# PG05__CELLS.net
KiCad netlist of a schematic drawn in Altium Designer
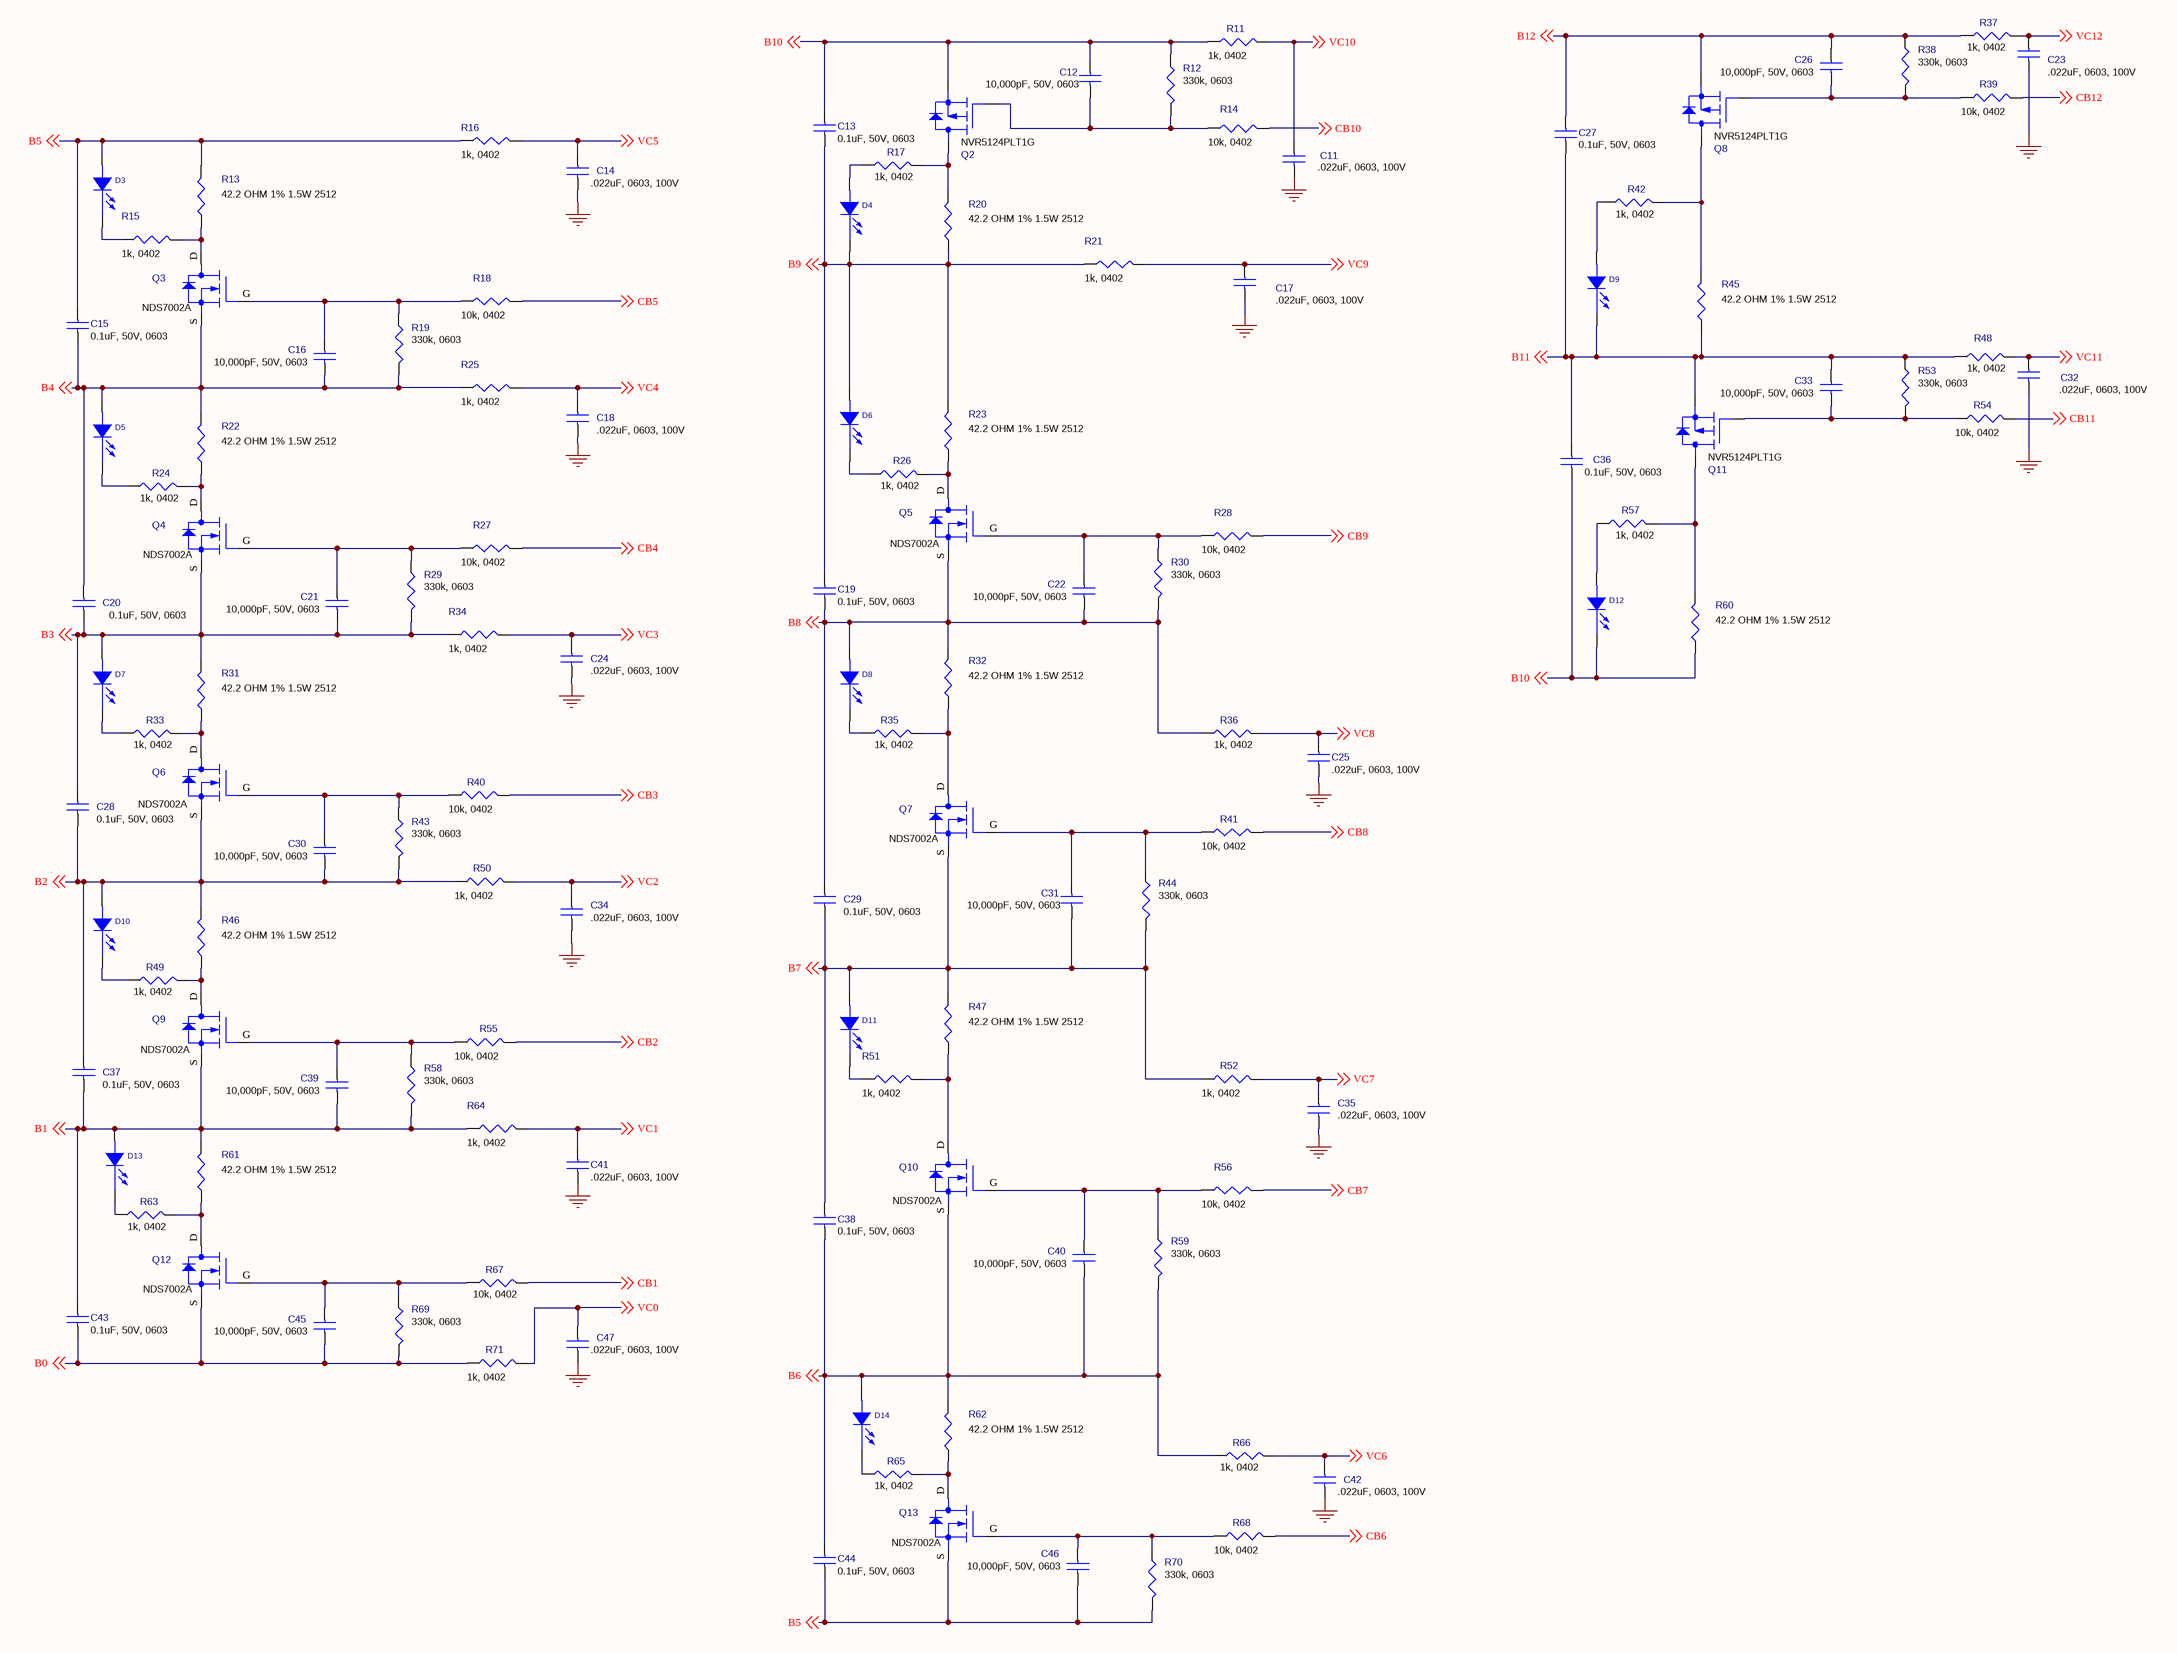
[diagram p0: PG05_ CELLS.SchDoc]

(export (version "E")
  (design (tool "Eeschema 10.0.6"))
  (components
    (comp (ref "C11")
      (value ".022uF, 0603, 100V")
      (footprint "C0603")
      (description "CAP CER 0.022UF 100V X7R 0603")
      (fields
        (field (name "MANUFACTURER") "Murata")
        (field (name "MANUFACTURER PART NUMBER") "GCJ188R72A223KA01D")
      )
      (libsource (lib "*") (part "CAP-Generic-0402"))
    )
    (comp (ref "C12")
      (value "10,000pF, 50V, 0603")
      (footprint "C0603")
      (description "CAP CER 10000PF 50V X7R 0603")
      (fields
        (field (name "MANUFACTURER") "TDK")
        (field (name "MANUFACTURER PART NUMBER") "CGA3E2X7R1H103K080AE")
      )
      (libsource (lib "*") (part "CAP-Generic-0603"))
    )
    (comp (ref "C13")
      (value "0.1uF, 50V, 0603")
      (footprint "C0603")
      (description "CAP CER 0.1UF 50V 10% X7R 0603")
      (fields
        (field (name "MANUFACTURER") "Murata")
        (field (name "MANUFACTURER PART NUMBER") "GCJ188R71E104KA12D")
      )
      (libsource (lib "*") (part "CAP-Generic-0603"))
    )
    (comp (ref "C14")
      (value ".022uF, 0603, 100V")
      (footprint "C0603")
      (description "CAP CER 0.022UF 100V X7R 0603")
      (fields
        (field (name "MANUFACTURER") "Murata")
        (field (name "MANUFACTURER PART NUMBER") "GCJ188R72A223KA01D")
      )
      (libsource (lib "*") (part "CAP-Generic-0402"))
    )
    (comp (ref "C15")
      (value "0.1uF, 50V, 0603")
      (footprint "C0603")
      (description "CAP CER 0.1UF 50V 10% X7R 0603")
      (fields
        (field (name "MANUFACTURER") "Murata")
        (field (name "MANUFACTURER PART NUMBER") "GCJ188R71E104KA12D")
      )
      (libsource (lib "*") (part "CAP-Generic-0603"))
    )
    (comp (ref "C16")
      (value "10,000pF, 50V, 0603")
      (footprint "C0603")
      (description "CAP CER 10000PF 50V X7R 0603")
      (fields
        (field (name "MANUFACTURER") "TDK")
        (field (name "MANUFACTURER PART NUMBER") "CGA3E2X7R1H103K080AE")
      )
      (libsource (lib "*") (part "CAP-Generic-0603"))
    )
    (comp (ref "C17")
      (value ".022uF, 0603, 100V")
      (footprint "C0603")
      (description "CAP CER 0.022UF 100V X7R 0603")
      (fields
        (field (name "MANUFACTURER") "Murata")
        (field (name "MANUFACTURER PART NUMBER") "GCJ188R72A223KA01D")
      )
      (libsource (lib "*") (part "CAP-Generic-0402"))
    )
    (comp (ref "C18")
      (value ".022uF, 0603, 100V")
      (footprint "C0603")
      (description "CAP CER 0.022UF 100V X7R 0603")
      (fields
        (field (name "MANUFACTURER") "Murata")
        (field (name "MANUFACTURER PART NUMBER") "GCJ188R72A223KA01D")
      )
      (libsource (lib "*") (part "CAP-Generic-0402"))
    )
    (comp (ref "C19")
      (value "0.1uF, 50V, 0603")
      (footprint "C0603")
      (description "CAP CER 0.1UF 50V 10% X7R 0603")
      (fields
        (field (name "MANUFACTURER") "Murata")
        (field (name "MANUFACTURER PART NUMBER") "GCJ188R71E104KA12D")
      )
      (libsource (lib "*") (part "CAP-Generic-0603"))
    )
    (comp (ref "C20")
      (value "0.1uF, 50V, 0603")
      (footprint "C0603")
      (description "CAP CER 0.1UF 50V 10% X7R 0603")
      (fields
        (field (name "MANUFACTURER") "Murata")
        (field (name "MANUFACTURER PART NUMBER") "GCJ188R71E104KA12D")
      )
      (libsource (lib "*") (part "CAP-Generic-0603"))
    )
    (comp (ref "C21")
      (value "10,000pF, 50V, 0603")
      (footprint "C0603")
      (description "CAP CER 10000PF 50V X7R 0603")
      (fields
        (field (name "MANUFACTURER") "TDK")
        (field (name "MANUFACTURER PART NUMBER") "CGA3E2X7R1H103K080AE")
      )
      (libsource (lib "*") (part "CAP-Generic-0603"))
    )
    (comp (ref "C22")
      (value "10,000pF, 50V, 0603")
      (footprint "C0603")
      (description "CAP CER 10000PF 50V X7R 0603")
      (fields
        (field (name "MANUFACTURER") "TDK")
        (field (name "MANUFACTURER PART NUMBER") "CGA3E2X7R1H103K080AE")
      )
      (libsource (lib "*") (part "CAP-Generic-0603"))
    )
    (comp (ref "C23")
      (value ".022uF, 0603, 100V")
      (footprint "C0603")
      (description "CAP CER 0.022UF 100V X7R 0603")
      (fields
        (field (name "MANUFACTURER") "Murata")
        (field (name "MANUFACTURER PART NUMBER") "GCJ188R72A223KA01D")
      )
      (libsource (lib "*") (part "CAP-Generic-0402"))
    )
    (comp (ref "C24")
      (value ".022uF, 0603, 100V")
      (footprint "C0603")
      (description "CAP CER 0.022UF 100V X7R 0603")
      (fields
        (field (name "MANUFACTURER") "Murata")
        (field (name "MANUFACTURER PART NUMBER") "GCJ188R72A223KA01D")
      )
      (libsource (lib "*") (part "CAP-Generic-0402"))
    )
    (comp (ref "C25")
      (value ".022uF, 0603, 100V")
      (footprint "C0603")
      (description "CAP CER 0.022UF 100V X7R 0603")
      (fields
        (field (name "MANUFACTURER") "Murata")
        (field (name "MANUFACTURER PART NUMBER") "GCJ188R72A223KA01D")
      )
      (libsource (lib "*") (part "CAP-Generic-0402"))
    )
    (comp (ref "C26")
      (value "10,000pF, 50V, 0603")
      (footprint "C0603")
      (description "CAP CER 10000PF 50V X7R 0603")
      (fields
        (field (name "MANUFACTURER") "TDK")
        (field (name "MANUFACTURER PART NUMBER") "CGA3E2X7R1H103K080AE")
      )
      (libsource (lib "*") (part "CAP-Generic-0603"))
    )
    (comp (ref "C27")
      (value "0.1uF, 50V, 0603")
      (footprint "C0603")
      (description "CAP CER 0.1UF 50V 10% X7R 0603")
      (fields
        (field (name "MANUFACTURER") "Murata")
        (field (name "MANUFACTURER PART NUMBER") "GCJ188R71E104KA12D")
      )
      (libsource (lib "*") (part "CAP-Generic-0603"))
    )
    (comp (ref "C28")
      (value "0.1uF, 50V, 0603")
      (footprint "C0603")
      (description "CAP CER 0.1UF 50V 10% X7R 0603")
      (fields
        (field (name "MANUFACTURER") "Murata")
        (field (name "MANUFACTURER PART NUMBER") "GCJ188R71E104KA12D")
      )
      (libsource (lib "*") (part "CAP-Generic-0603"))
    )
    (comp (ref "C29")
      (value "0.1uF, 50V, 0603")
      (footprint "C0603")
      (description "CAP CER 0.1UF 50V 10% X7R 0603")
      (fields
        (field (name "MANUFACTURER") "Murata")
        (field (name "MANUFACTURER PART NUMBER") "GCJ188R71E104KA12D")
      )
      (libsource (lib "*") (part "CAP-Generic-0603"))
    )
    (comp (ref "C30")
      (value "10,000pF, 50V, 0603")
      (footprint "C0603")
      (description "CAP CER 10000PF 50V X7R 0603")
      (fields
        (field (name "MANUFACTURER") "TDK")
        (field (name "MANUFACTURER PART NUMBER") "CGA3E2X7R1H103K080AE")
      )
      (libsource (lib "*") (part "CAP-Generic-0603"))
    )
    (comp (ref "C31")
      (value "10,000pF, 50V, 0603")
      (footprint "C0603")
      (description "CAP CER 10000PF 50V X7R 0603")
      (fields
        (field (name "MANUFACTURER") "TDK")
        (field (name "MANUFACTURER PART NUMBER") "CGA3E2X7R1H103K080AE")
      )
      (libsource (lib "*") (part "CAP-Generic-0603"))
    )
    (comp (ref "C32")
      (value ".022uF, 0603, 100V")
      (footprint "C0603")
      (description "CAP CER 0.022UF 100V X7R 0603")
      (fields
        (field (name "MANUFACTURER") "Murata")
        (field (name "MANUFACTURER PART NUMBER") "GCJ188R72A223KA01D")
      )
      (libsource (lib "*") (part "CAP-Generic-0402"))
    )
    (comp (ref "C33")
      (value "10,000pF, 50V, 0603")
      (footprint "C0603")
      (description "CAP CER 10000PF 50V X7R 0603")
      (fields
        (field (name "MANUFACTURER") "TDK")
        (field (name "MANUFACTURER PART NUMBER") "CGA3E2X7R1H103K080AE")
      )
      (libsource (lib "*") (part "CAP-Generic-0603"))
    )
    (comp (ref "C34")
      (value ".022uF, 0603, 100V")
      (footprint "C0603")
      (description "CAP CER 0.022UF 100V X7R 0603")
      (fields
        (field (name "MANUFACTURER") "Murata")
        (field (name "MANUFACTURER PART NUMBER") "GCJ188R72A223KA01D")
      )
      (libsource (lib "*") (part "CAP-Generic-0402"))
    )
    (comp (ref "C35")
      (value ".022uF, 0603, 100V")
      (footprint "C0603")
      (description "CAP CER 0.022UF 100V X7R 0603")
      (fields
        (field (name "MANUFACTURER") "Murata")
        (field (name "MANUFACTURER PART NUMBER") "GCJ188R72A223KA01D")
      )
      (libsource (lib "*") (part "CAP-Generic-0402"))
    )
    (comp (ref "C36")
      (value "0.1uF, 50V, 0603")
      (footprint "C0603")
      (description "CAP CER 0.1UF 50V 10% X7R 0603")
      (fields
        (field (name "MANUFACTURER") "Murata")
        (field (name "MANUFACTURER PART NUMBER") "GCJ188R71E104KA12D")
      )
      (libsource (lib "*") (part "CAP-Generic-0603"))
    )
    (comp (ref "C37")
      (value "0.1uF, 50V, 0603")
      (footprint "C0603")
      (description "CAP CER 0.1UF 50V 10% X7R 0603")
      (fields
        (field (name "MANUFACTURER") "Murata")
        (field (name "MANUFACTURER PART NUMBER") "GCJ188R71E104KA12D")
      )
      (libsource (lib "*") (part "CAP-Generic-0603"))
    )
    (comp (ref "C38")
      (value "0.1uF, 50V, 0603")
      (footprint "C0603")
      (description "CAP CER 0.1UF 50V 10% X7R 0603")
      (fields
        (field (name "MANUFACTURER") "Murata")
        (field (name "MANUFACTURER PART NUMBER") "GCJ188R71E104KA12D")
      )
      (libsource (lib "*") (part "CAP-Generic-0603"))
    )
    (comp (ref "C39")
      (value "10,000pF, 50V, 0603")
      (footprint "C0603")
      (description "CAP CER 10000PF 50V X7R 0603")
      (fields
        (field (name "MANUFACTURER") "TDK")
        (field (name "MANUFACTURER PART NUMBER") "CGA3E2X7R1H103K080AE")
      )
      (libsource (lib "*") (part "CAP-Generic-0603"))
    )
    (comp (ref "C40")
      (value "10,000pF, 50V, 0603")
      (footprint "C0603")
      (description "CAP CER 10000PF 50V X7R 0603")
      (fields
        (field (name "MANUFACTURER") "TDK")
        (field (name "MANUFACTURER PART NUMBER") "CGA3E2X7R1H103K080AE")
      )
      (libsource (lib "*") (part "CAP-Generic-0603"))
    )
    (comp (ref "C41")
      (value ".022uF, 0603, 100V")
      (footprint "C0603")
      (description "CAP CER 0.022UF 100V X7R 0603")
      (fields
        (field (name "MANUFACTURER") "Murata")
        (field (name "MANUFACTURER PART NUMBER") "GCJ188R72A223KA01D")
      )
      (libsource (lib "*") (part "CAP-Generic-0402"))
    )
    (comp (ref "C42")
      (value ".022uF, 0603, 100V")
      (footprint "C0603")
      (description "CAP CER 0.022UF 100V X7R 0603")
      (fields
        (field (name "MANUFACTURER") "Murata")
        (field (name "MANUFACTURER PART NUMBER") "GCJ188R72A223KA01D")
      )
      (libsource (lib "*") (part "CAP-Generic-0402"))
    )
    (comp (ref "C43")
      (value "0.1uF, 50V, 0603")
      (footprint "C0603")
      (description "CAP CER 0.1UF 50V 10% X7R 0603")
      (fields
        (field (name "MANUFACTURER") "Murata")
        (field (name "MANUFACTURER PART NUMBER") "GCJ188R71E104KA12D")
      )
      (libsource (lib "*") (part "CAP-Generic-0603"))
    )
    (comp (ref "C44")
      (value "0.1uF, 50V, 0603")
      (footprint "C0603")
      (description "CAP CER 0.1UF 50V 10% X7R 0603")
      (fields
        (field (name "MANUFACTURER") "Murata")
        (field (name "MANUFACTURER PART NUMBER") "GCJ188R71E104KA12D")
      )
      (libsource (lib "*") (part "CAP-Generic-0603"))
    )
    (comp (ref "C45")
      (value "10,000pF, 50V, 0603")
      (footprint "C0603")
      (description "CAP CER 10000PF 50V X7R 0603")
      (fields
        (field (name "MANUFACTURER") "TDK")
        (field (name "MANUFACTURER PART NUMBER") "CGA3E2X7R1H103K080AE")
      )
      (libsource (lib "*") (part "CAP-Generic-0603"))
    )
    (comp (ref "C46")
      (value "10,000pF, 50V, 0603")
      (footprint "C0603")
      (description "CAP CER 10000PF 50V X7R 0603")
      (fields
        (field (name "MANUFACTURER") "TDK")
        (field (name "MANUFACTURER PART NUMBER") "CGA3E2X7R1H103K080AE")
      )
      (libsource (lib "*") (part "CAP-Generic-0603"))
    )
    (comp (ref "C47")
      (value ".022uF, 0603, 100V")
      (footprint "C0603")
      (description "CAP CER 0.022UF 100V X7R 0603")
      (fields
        (field (name "MANUFACTURER") "Murata")
        (field (name "MANUFACTURER PART NUMBER") "GCJ188R72A223KA01D")
      )
      (libsource (lib "*") (part "CAP-Generic-0402"))
    )
    (comp (ref "D3")
      (value "SML-P12MTT86R, 0402")
      (footprint "D0402")
      (libsource (lib "M2_V8_BMU_V1.0") (part "LED-GENERIC"))
    )
    (comp (ref "D4")
      (value "SML-P12MTT86R, 0402")
      (footprint "D0402")
      (libsource (lib "M2_V8_BMU_V1.0") (part "LED-GENERIC"))
    )
    (comp (ref "D5")
      (value "SML-P12MTT86R, 0402")
      (footprint "D0402")
      (libsource (lib "M2_V8_BMU_V1.0") (part "LED-GENERIC"))
    )
    (comp (ref "D6")
      (value "SML-P12MTT86R, 0402")
      (footprint "D0402")
      (libsource (lib "M2_V8_BMU_V1.0") (part "LED-GENERIC"))
    )
    (comp (ref "D7")
      (value "SML-P12MTT86R, 0402")
      (footprint "D0402")
      (libsource (lib "M2_V8_BMU_V1.0") (part "LED-GENERIC"))
    )
    (comp (ref "D8")
      (value "SML-P12MTT86R, 0402")
      (footprint "D0402")
      (libsource (lib "M2_V8_BMU_V1.0") (part "LED-GENERIC"))
    )
    (comp (ref "D9")
      (value "SML-P12MTT86R, 0402")
      (footprint "D0402")
      (libsource (lib "M2_V8_BMU_V1.0") (part "LED-GENERIC"))
    )
    (comp (ref "D10")
      (value "SML-P12MTT86R, 0402")
      (footprint "D0402")
      (libsource (lib "M2_V8_BMU_V1.0") (part "LED-GENERIC"))
    )
    (comp (ref "D11")
      (value "SML-P12MTT86R, 0402")
      (footprint "D0402")
      (libsource (lib "M2_V8_BMU_V1.0") (part "LED-GENERIC"))
    )
    (comp (ref "D12")
      (value "SML-P12MTT86R, 0402")
      (footprint "D0402")
      (libsource (lib "M2_V8_BMU_V1.0") (part "LED-GENERIC"))
    )
    (comp (ref "D13")
      (value "SML-P12MTT86R, 0402")
      (footprint "D0402")
      (libsource (lib "M2_V8_BMU_V1.0") (part "LED-GENERIC"))
    )
    (comp (ref "D14")
      (value "SML-P12MTT86R, 0402")
      (footprint "D0402")
      (libsource (lib "M2_V8_BMU_V1.0") (part "LED-GENERIC"))
    )
    (comp (ref "Q2")
      (value "NVR5124PLT1G")
      (footprint "SOT-23")
      (description "MOSFET P-CH 60V 1.1A SOT-23")
      (fields (field (name "MANUFACTURER") "ON Semiconductor"))
      (libsource (lib "*") (part "FET-P-CH-Generic_OP4_0"))
    )
    (comp (ref "Q3")
      (value "NDS7002A")
      (footprint "SOT-23")
      (description "MOSFET N-CH 60V 280MA SOT-23")
      (fields (field (name "MANUFACTURER") "ON Semiconductor / Fairchild") (field (name "VOLTAGE") "60V"))
      (libsource (lib "*") (part "FET-NCH-GenericOp2"))
    )
    (comp (ref "Q4")
      (value "NDS7002A")
      (footprint "SOT-23")
      (description "MOSFET N-CH 60V 280MA SOT-23")
      (fields (field (name "MANUFACTURER") "ON Semiconductor / Fairchild") (field (name "VOLTAGE") "60V"))
      (libsource (lib "*") (part "FET-NCH-GenericOp2"))
    )
    (comp (ref "Q5")
      (value "NDS7002A")
      (footprint "SOT-23")
      (description "MOSFET N-CH 60V 280MA SOT-23")
      (fields (field (name "MANUFACTURER") "ON Semiconductor / Fairchild") (field (name "VOLTAGE") "60V"))
      (libsource (lib "*") (part "FET-NCH-GenericOp2"))
    )
    (comp (ref "Q6")
      (value "NDS7002A")
      (footprint "SOT-23")
      (description "MOSFET N-CH 60V 280MA SOT-23")
      (fields (field (name "MANUFACTURER") "ON Semiconductor / Fairchild") (field (name "VOLTAGE") "60V"))
      (libsource (lib "*") (part "FET-NCH-GenericOp2"))
    )
    (comp (ref "Q7")
      (value "NDS7002A")
      (footprint "SOT-23")
      (description "MOSFET N-CH 60V 280MA SOT-23")
      (fields (field (name "MANUFACTURER") "ON Semiconductor / Fairchild") (field (name "VOLTAGE") "60V"))
      (libsource (lib "*") (part "FET-NCH-GenericOp2"))
    )
    (comp (ref "Q8")
      (value "NVR5124PLT1G")
      (footprint "SOT-23")
      (description "MOSFET P-CH 60V 1.1A SOT-23")
      (fields (field (name "MANUFACTURER") "ON Semiconductor"))
      (libsource (lib "*") (part "FET-P-CH-Generic_OP4_0"))
    )
    (comp (ref "Q9")
      (value "NDS7002A")
      (footprint "SOT-23")
      (description "MOSFET N-CH 60V 280MA SOT-23")
      (fields (field (name "MANUFACTURER") "ON Semiconductor / Fairchild") (field (name "VOLTAGE") "60V"))
      (libsource (lib "*") (part "FET-NCH-GenericOp2"))
    )
    (comp (ref "Q10")
      (value "NDS7002A")
      (footprint "SOT-23")
      (description "MOSFET N-CH 60V 280MA SOT-23")
      (fields (field (name "MANUFACTURER") "ON Semiconductor / Fairchild") (field (name "VOLTAGE") "60V"))
      (libsource (lib "*") (part "FET-NCH-GenericOp2"))
    )
    (comp (ref "Q11")
      (value "NVR5124PLT1G")
      (footprint "SOT-23")
      (description "MOSFET P-CH 60V 1.1A SOT-23")
      (fields (field (name "MANUFACTURER") "ON Semiconductor"))
      (libsource (lib "*") (part "FET-P-CH-Generic_OP4_0"))
    )
    (comp (ref "Q12")
      (value "NDS7002A")
      (footprint "SOT-23")
      (description "MOSFET N-CH 60V 280MA SOT-23")
      (fields (field (name "MANUFACTURER") "ON Semiconductor / Fairchild") (field (name "VOLTAGE") "60V"))
      (libsource (lib "*") (part "FET-NCH-GenericOp2"))
    )
    (comp (ref "Q13")
      (value "NDS7002A")
      (footprint "SOT-23")
      (description "MOSFET N-CH 60V 280MA SOT-23")
      (fields (field (name "MANUFACTURER") "ON Semiconductor / Fairchild") (field (name "VOLTAGE") "60V"))
      (libsource (lib "*") (part "FET-NCH-GenericOp2"))
    )
    (comp (ref "R11")
      (value "1k, 0402")
      (footprint "R0402")
      (description "RES SMD 1K OHM 5% 1/16W 0402")
      (fields
        (field (name "MANUFACTURER") "Yageo")
        (field (name "MANUFACTURER PART NUMBER") "RC0402JR-071KL")
      )
      (libsource (lib "*") (part "R-Generic-0402"))
    )
    (comp (ref "R12")
      (value "330k, 0603")
      (footprint "R0603")
      (description "RES SMD 330K OHM 5% 1/10W 0603")
      (fields
        (field (name "MANUFACTURER") "Yageo")
        (field (name "MANUFACTURER PART NUMBER") "RC0603JR-07330KL")
      )
      (libsource (lib "*") (part "R-Generic-0603"))
    )
    (comp (ref "R13")
      (value "42.2 OHM 1% 1.5W 2512")
      (footprint "2512")
      (description "RES SMD 42.2 OHM 1% 1.5W 2512")
      (fields
        (field (name "MANUFACTURER") "Vishay Dale")
        (field (name "MANUFACTURER PART NUMBER") "CRCW251242R2FKEGHP")
      )
      (libsource (lib "*") (part "R-Generic"))
    )
    (comp (ref "R14")
      (value "10k, 0402")
      (footprint "R0402")
      (description "RES SMD 10K OHM 1% 1/16W 0402")
      (fields
        (field (name "MANUFACTURER") "Vishay Dale")
        (field (name "MANUFACTURER PART NUMBER") "CRCW040210K0FKTD")
      )
      (libsource (lib "Miscellaneous Devices") (part "R-Generic-0402"))
    )
    (comp (ref "R15")
      (value "1k, 0402")
      (footprint "R0402")
      (description "RES SMD 1K OHM 5% 1/16W 0402")
      (fields
        (field (name "MANUFACTURER") "Yageo")
        (field (name "MANUFACTURER PART NUMBER") "RC0402JR-071KL")
      )
      (libsource (lib "*") (part "R-Generic-0402"))
    )
    (comp (ref "R16")
      (value "1k, 0402")
      (footprint "R0402")
      (description "RES SMD 1K OHM 5% 1/16W 0402")
      (fields
        (field (name "MANUFACTURER") "Yageo")
        (field (name "MANUFACTURER PART NUMBER") "RC0402JR-071KL")
      )
      (libsource (lib "*") (part "R-Generic-0402"))
    )
    (comp (ref "R17")
      (value "1k, 0402")
      (footprint "R0402")
      (description "RES SMD 1K OHM 5% 1/16W 0402")
      (fields
        (field (name "MANUFACTURER") "Yageo")
        (field (name "MANUFACTURER PART NUMBER") "RC0402JR-071KL")
      )
      (libsource (lib "*") (part "R-Generic-0402"))
    )
    (comp (ref "R18")
      (value "10k, 0402")
      (footprint "R0402")
      (description "RES SMD 10K OHM 1% 1/16W 0402")
      (fields
        (field (name "MANUFACTURER") "Vishay Dale")
        (field (name "MANUFACTURER PART NUMBER") "CRCW040210K0FKTD")
      )
      (libsource (lib "Miscellaneous Devices") (part "R-Generic-0402"))
    )
    (comp (ref "R19")
      (value "330k, 0603")
      (footprint "R0603")
      (description "RES SMD 330K OHM 5% 1/10W 0603")
      (fields
        (field (name "MANUFACTURER") "Yageo")
        (field (name "MANUFACTURER PART NUMBER") "RC0603JR-07330KL")
      )
      (libsource (lib "*") (part "R-Generic-0603"))
    )
    (comp (ref "R20")
      (value "42.2 OHM 1% 1.5W 2512")
      (footprint "2512")
      (description "RES SMD 42.2 OHM 1% 1.5W 2512")
      (fields
        (field (name "MANUFACTURER") "Vishay Dale")
        (field (name "MANUFACTURER PART NUMBER") "CRCW251242R2FKEGHP")
      )
      (libsource (lib "*") (part "R-Generic"))
    )
    (comp (ref "R21")
      (value "1k, 0402")
      (footprint "R0402")
      (description "RES SMD 1K OHM 5% 1/16W 0402")
      (fields
        (field (name "MANUFACTURER") "Yageo")
        (field (name "MANUFACTURER PART NUMBER") "RC0402JR-071KL")
      )
      (libsource (lib "*") (part "R-Generic-0402"))
    )
    (comp (ref "R22")
      (value "42.2 OHM 1% 1.5W 2512")
      (footprint "2512")
      (description "RES SMD 42.2 OHM 1% 1.5W 2512")
      (fields
        (field (name "MANUFACTURER") "Vishay Dale")
        (field (name "MANUFACTURER PART NUMBER") "CRCW251242R2FKEGHP")
      )
      (libsource (lib "*") (part "R-Generic"))
    )
    (comp (ref "R23")
      (value "42.2 OHM 1% 1.5W 2512")
      (footprint "2512")
      (description "RES SMD 42.2 OHM 1% 1.5W 2512")
      (fields
        (field (name "MANUFACTURER") "Vishay Dale")
        (field (name "MANUFACTURER PART NUMBER") "CRCW251242R2FKEGHP")
      )
      (libsource (lib "*") (part "R-Generic"))
    )
    (comp (ref "R24")
      (value "1k, 0402")
      (footprint "R0402")
      (description "RES SMD 1K OHM 5% 1/16W 0402")
      (fields
        (field (name "MANUFACTURER") "Yageo")
        (field (name "MANUFACTURER PART NUMBER") "RC0402JR-071KL")
      )
      (libsource (lib "*") (part "R-Generic-0402"))
    )
    (comp (ref "R25")
      (value "1k, 0402")
      (footprint "R0402")
      (description "RES SMD 1K OHM 5% 1/16W 0402")
      (fields
        (field (name "MANUFACTURER") "Yageo")
        (field (name "MANUFACTURER PART NUMBER") "RC0402JR-071KL")
      )
      (libsource (lib "*") (part "R-Generic-0402"))
    )
    (comp (ref "R26")
      (value "1k, 0402")
      (footprint "R0402")
      (description "RES SMD 1K OHM 5% 1/16W 0402")
      (fields
        (field (name "MANUFACTURER") "Yageo")
        (field (name "MANUFACTURER PART NUMBER") "RC0402JR-071KL")
      )
      (libsource (lib "*") (part "R-Generic-0402"))
    )
    (comp (ref "R27")
      (value "10k, 0402")
      (footprint "R0402")
      (description "RES SMD 10K OHM 1% 1/16W 0402")
      (fields
        (field (name "MANUFACTURER") "Vishay Dale")
        (field (name "MANUFACTURER PART NUMBER") "CRCW040210K0FKTD")
      )
      (libsource (lib "Miscellaneous Devices") (part "R-Generic-0402"))
    )
    (comp (ref "R28")
      (value "10k, 0402")
      (footprint "R0402")
      (description "RES SMD 10K OHM 1% 1/16W 0402")
      (fields
        (field (name "MANUFACTURER") "Vishay Dale")
        (field (name "MANUFACTURER PART NUMBER") "CRCW040210K0FKTD")
      )
      (libsource (lib "Miscellaneous Devices") (part "R-Generic-0402"))
    )
    (comp (ref "R29")
      (value "330k, 0603")
      (footprint "R0603")
      (description "RES SMD 330K OHM 5% 1/10W 0603")
      (fields
        (field (name "MANUFACTURER") "Yageo")
        (field (name "MANUFACTURER PART NUMBER") "RC0603JR-07330KL")
      )
      (libsource (lib "*") (part "R-Generic-0603"))
    )
    (comp (ref "R30")
      (value "330k, 0603")
      (footprint "R0603")
      (description "RES SMD 330K OHM 5% 1/10W 0603")
      (fields
        (field (name "MANUFACTURER") "Yageo")
        (field (name "MANUFACTURER PART NUMBER") "RC0603JR-07330KL")
      )
      (libsource (lib "*") (part "R-Generic-0603"))
    )
    (comp (ref "R31")
      (value "42.2 OHM 1% 1.5W 2512")
      (footprint "2512")
      (description "RES SMD 42.2 OHM 1% 1.5W 2512")
      (fields
        (field (name "MANUFACTURER") "Vishay Dale")
        (field (name "MANUFACTURER PART NUMBER") "CRCW251242R2FKEGHP")
      )
      (libsource (lib "*") (part "R-Generic"))
    )
    (comp (ref "R32")
      (value "42.2 OHM 1% 1.5W 2512")
      (footprint "2512")
      (description "RES SMD 42.2 OHM 1% 1.5W 2512")
      (fields
        (field (name "MANUFACTURER") "Vishay Dale")
        (field (name "MANUFACTURER PART NUMBER") "CRCW251242R2FKEGHP")
      )
      (libsource (lib "*") (part "R-Generic"))
    )
    (comp (ref "R33")
      (value "1k, 0402")
      (footprint "R0402")
      (description "RES SMD 1K OHM 5% 1/16W 0402")
      (fields
        (field (name "MANUFACTURER") "Yageo")
        (field (name "MANUFACTURER PART NUMBER") "RC0402JR-071KL")
      )
      (libsource (lib "*") (part "R-Generic-0402"))
    )
    (comp (ref "R34")
      (value "1k, 0402")
      (footprint "R0402")
      (description "RES SMD 1K OHM 5% 1/16W 0402")
      (fields
        (field (name "MANUFACTURER") "Yageo")
        (field (name "MANUFACTURER PART NUMBER") "RC0402JR-071KL")
      )
      (libsource (lib "*") (part "R-Generic-0402"))
    )
    (comp (ref "R35")
      (value "1k, 0402")
      (footprint "R0402")
      (description "RES SMD 1K OHM 5% 1/16W 0402")
      (fields
        (field (name "MANUFACTURER") "Yageo")
        (field (name "MANUFACTURER PART NUMBER") "RC0402JR-071KL")
      )
      (libsource (lib "*") (part "R-Generic-0402"))
    )
    (comp (ref "R36")
      (value "1k, 0402")
      (footprint "R0402")
      (description "RES SMD 1K OHM 5% 1/16W 0402")
      (fields
        (field (name "MANUFACTURER") "Yageo")
        (field (name "MANUFACTURER PART NUMBER") "RC0402JR-071KL")
      )
      (libsource (lib "*") (part "R-Generic-0402"))
    )
    (comp (ref "R37")
      (value "1k, 0402")
      (footprint "R0402")
      (description "RES SMD 1K OHM 5% 1/16W 0402")
      (fields
        (field (name "MANUFACTURER") "Yageo")
        (field (name "MANUFACTURER PART NUMBER") "RC0402JR-071KL")
      )
      (libsource (lib "*") (part "R-Generic-0402"))
    )
    (comp (ref "R38")
      (value "330k, 0603")
      (footprint "R0603")
      (description "RES SMD 330K OHM 5% 1/10W 0603")
      (fields
        (field (name "MANUFACTURER") "Yageo")
        (field (name "MANUFACTURER PART NUMBER") "RC0603JR-07330KL")
      )
      (libsource (lib "*") (part "R-Generic-0603"))
    )
    (comp (ref "R39")
      (value "10k, 0402")
      (footprint "R0402")
      (description "RES SMD 10K OHM 1% 1/16W 0402")
      (fields
        (field (name "MANUFACTURER") "Vishay Dale")
        (field (name "MANUFACTURER PART NUMBER") "CRCW040210K0FKTD")
      )
      (libsource (lib "Miscellaneous Devices") (part "R-Generic-0402"))
    )
    (comp (ref "R40")
      (value "10k, 0402")
      (footprint "R0402")
      (description "RES SMD 10K OHM 1% 1/16W 0402")
      (fields
        (field (name "MANUFACTURER") "Vishay Dale")
        (field (name "MANUFACTURER PART NUMBER") "CRCW040210K0FKTD")
      )
      (libsource (lib "Miscellaneous Devices") (part "R-Generic-0402"))
    )
    (comp (ref "R41")
      (value "10k, 0402")
      (footprint "R0402")
      (description "RES SMD 10K OHM 1% 1/16W 0402")
      (fields
        (field (name "MANUFACTURER") "Vishay Dale")
        (field (name "MANUFACTURER PART NUMBER") "CRCW040210K0FKTD")
      )
      (libsource (lib "Miscellaneous Devices") (part "R-Generic-0402"))
    )
    (comp (ref "R42")
      (value "1k, 0402")
      (footprint "R0402")
      (description "RES SMD 1K OHM 5% 1/16W 0402")
      (fields
        (field (name "MANUFACTURER") "Yageo")
        (field (name "MANUFACTURER PART NUMBER") "RC0402JR-071KL")
      )
      (libsource (lib "*") (part "R-Generic-0402"))
    )
    (comp (ref "R43")
      (value "330k, 0603")
      (footprint "R0603")
      (description "RES SMD 330K OHM 5% 1/10W 0603")
      (fields
        (field (name "MANUFACTURER") "Yageo")
        (field (name "MANUFACTURER PART NUMBER") "RC0603JR-07330KL")
      )
      (libsource (lib "*") (part "R-Generic-0603"))
    )
    (comp (ref "R44")
      (value "330k, 0603")
      (footprint "R0603")
      (description "RES SMD 330K OHM 5% 1/10W 0603")
      (fields
        (field (name "MANUFACTURER") "Yageo")
        (field (name "MANUFACTURER PART NUMBER") "RC0603JR-07330KL")
      )
      (libsource (lib "*") (part "R-Generic-0603"))
    )
    (comp (ref "R45")
      (value "42.2 OHM 1% 1.5W 2512")
      (footprint "2512")
      (description "RES SMD 42.2 OHM 1% 1.5W 2512")
      (fields
        (field (name "MANUFACTURER") "Vishay Dale")
        (field (name "MANUFACTURER PART NUMBER") "CRCW251242R2FKEGHP")
      )
      (libsource (lib "*") (part "R-Generic"))
    )
    (comp (ref "R46")
      (value "42.2 OHM 1% 1.5W 2512")
      (footprint "2512")
      (description "RES SMD 42.2 OHM 1% 1.5W 2512")
      (fields
        (field (name "MANUFACTURER") "Vishay Dale")
        (field (name "MANUFACTURER PART NUMBER") "CRCW251242R2FKEGHP")
      )
      (libsource (lib "*") (part "R-Generic"))
    )
    (comp (ref "R47")
      (value "42.2 OHM 1% 1.5W 2512")
      (footprint "2512")
      (description "RES SMD 42.2 OHM 1% 1.5W 2512")
      (fields
        (field (name "MANUFACTURER") "Vishay Dale")
        (field (name "MANUFACTURER PART NUMBER") "CRCW251242R2FKEGHP")
      )
      (libsource (lib "*") (part "R-Generic"))
    )
    (comp (ref "R48")
      (value "1k, 0402")
      (footprint "R0402")
      (description "RES SMD 1K OHM 5% 1/16W 0402")
      (fields
        (field (name "MANUFACTURER") "Yageo")
        (field (name "MANUFACTURER PART NUMBER") "RC0402JR-071KL")
      )
      (libsource (lib "*") (part "R-Generic-0402"))
    )
    (comp (ref "R49")
      (value "1k, 0402")
      (footprint "R0402")
      (description "RES SMD 1K OHM 5% 1/16W 0402")
      (fields
        (field (name "MANUFACTURER") "Yageo")
        (field (name "MANUFACTURER PART NUMBER") "RC0402JR-071KL")
      )
      (libsource (lib "*") (part "R-Generic-0402"))
    )
    (comp (ref "R50")
      (value "1k, 0402")
      (footprint "R0402")
      (description "RES SMD 1K OHM 5% 1/16W 0402")
      (fields
        (field (name "MANUFACTURER") "Yageo")
        (field (name "MANUFACTURER PART NUMBER") "RC0402JR-071KL")
      )
      (libsource (lib "*") (part "R-Generic-0402"))
    )
    (comp (ref "R51")
      (value "1k, 0402")
      (footprint "R0402")
      (description "RES SMD 1K OHM 5% 1/16W 0402")
      (fields
        (field (name "MANUFACTURER") "Yageo")
        (field (name "MANUFACTURER PART NUMBER") "RC0402JR-071KL")
      )
      (libsource (lib "*") (part "R-Generic-0402"))
    )
    (comp (ref "R52")
      (value "1k, 0402")
      (footprint "R0402")
      (description "RES SMD 1K OHM 5% 1/16W 0402")
      (fields
        (field (name "MANUFACTURER") "Yageo")
        (field (name "MANUFACTURER PART NUMBER") "RC0402JR-071KL")
      )
      (libsource (lib "*") (part "R-Generic-0402"))
    )
    (comp (ref "R53")
      (value "330k, 0603")
      (footprint "R0603")
      (description "RES SMD 330K OHM 5% 1/10W 0603")
      (fields
        (field (name "MANUFACTURER") "Yageo")
        (field (name "MANUFACTURER PART NUMBER") "RC0603JR-07330KL")
      )
      (libsource (lib "*") (part "R-Generic-0603"))
    )
    (comp (ref "R54")
      (value "10k, 0402")
      (footprint "R0402")
      (description "RES SMD 10K OHM 1% 1/16W 0402")
      (fields
        (field (name "MANUFACTURER") "Vishay Dale")
        (field (name "MANUFACTURER PART NUMBER") "CRCW040210K0FKTD")
      )
      (libsource (lib "Miscellaneous Devices") (part "R-Generic-0402"))
    )
    (comp (ref "R55")
      (value "10k, 0402")
      (footprint "R0402")
      (description "RES SMD 10K OHM 1% 1/16W 0402")
      (fields
        (field (name "MANUFACTURER") "Vishay Dale")
        (field (name "MANUFACTURER PART NUMBER") "CRCW040210K0FKTD")
      )
      (libsource (lib "Miscellaneous Devices") (part "R-Generic-0402"))
    )
    (comp (ref "R56")
      (value "10k, 0402")
      (footprint "R0402")
      (description "RES SMD 10K OHM 1% 1/16W 0402")
      (fields
        (field (name "MANUFACTURER") "Vishay Dale")
        (field (name "MANUFACTURER PART NUMBER") "CRCW040210K0FKTD")
      )
      (libsource (lib "Miscellaneous Devices") (part "R-Generic-0402"))
    )
    (comp (ref "R57")
      (value "1k, 0402")
      (footprint "R0402")
      (description "RES SMD 1K OHM 5% 1/16W 0402")
      (fields
        (field (name "MANUFACTURER") "Yageo")
        (field (name "MANUFACTURER PART NUMBER") "RC0402JR-071KL")
      )
      (libsource (lib "*") (part "R-Generic-0402"))
    )
    (comp (ref "R58")
      (value "330k, 0603")
      (footprint "R0603")
      (description "RES SMD 330K OHM 5% 1/10W 0603")
      (fields
        (field (name "MANUFACTURER") "Yageo")
        (field (name "MANUFACTURER PART NUMBER") "RC0603JR-07330KL")
      )
      (libsource (lib "*") (part "R-Generic-0603"))
    )
    (comp (ref "R59")
      (value "330k, 0603")
      (footprint "R0603")
      (description "RES SMD 330K OHM 5% 1/10W 0603")
      (fields
        (field (name "MANUFACTURER") "Yageo")
        (field (name "MANUFACTURER PART NUMBER") "RC0603JR-07330KL")
      )
      (libsource (lib "*") (part "R-Generic-0603"))
    )
    (comp (ref "R60")
      (value "42.2 OHM 1% 1.5W 2512")
      (footprint "2512")
      (description "RES SMD 42.2 OHM 1% 1.5W 2512")
      (fields
        (field (name "MANUFACTURER") "Vishay Dale")
        (field (name "MANUFACTURER PART NUMBER") "CRCW251242R2FKEGHP")
      )
      (libsource (lib "*") (part "R-Generic"))
    )
    (comp (ref "R61")
      (value "42.2 OHM 1% 1.5W 2512")
      (footprint "2512")
      (description "RES SMD 42.2 OHM 1% 1.5W 2512")
      (fields
        (field (name "MANUFACTURER") "Vishay Dale")
        (field (name "MANUFACTURER PART NUMBER") "CRCW251242R2FKEGHP")
      )
      (libsource (lib "*") (part "R-Generic"))
    )
    (comp (ref "R62")
      (value "42.2 OHM 1% 1.5W 2512")
      (footprint "2512")
      (description "RES SMD 42.2 OHM 1% 1.5W 2512")
      (fields
        (field (name "MANUFACTURER") "Vishay Dale")
        (field (name "MANUFACTURER PART NUMBER") "CRCW251242R2FKEGHP")
      )
      (libsource (lib "*") (part "R-Generic"))
    )
    (comp (ref "R63")
      (value "1k, 0402")
      (footprint "R0402")
      (description "RES SMD 1K OHM 5% 1/16W 0402")
      (fields
        (field (name "MANUFACTURER") "Yageo")
        (field (name "MANUFACTURER PART NUMBER") "RC0402JR-071KL")
      )
      (libsource (lib "*") (part "R-Generic-0402"))
    )
    (comp (ref "R64")
      (value "1k, 0402")
      (footprint "R0402")
      (description "RES SMD 1K OHM 5% 1/16W 0402")
      (fields
        (field (name "MANUFACTURER") "Yageo")
        (field (name "MANUFACTURER PART NUMBER") "RC0402JR-071KL")
      )
      (libsource (lib "*") (part "R-Generic-0402"))
    )
    (comp (ref "R65")
      (value "1k, 0402")
      (footprint "R0402")
      (description "RES SMD 1K OHM 5% 1/16W 0402")
      (fields
        (field (name "MANUFACTURER") "Yageo")
        (field (name "MANUFACTURER PART NUMBER") "RC0402JR-071KL")
      )
      (libsource (lib "*") (part "R-Generic-0402"))
    )
    (comp (ref "R66")
      (value "1k, 0402")
      (footprint "R0402")
      (description "RES SMD 1K OHM 5% 1/16W 0402")
      (fields
        (field (name "MANUFACTURER") "Yageo")
        (field (name "MANUFACTURER PART NUMBER") "RC0402JR-071KL")
      )
      (libsource (lib "*") (part "R-Generic-0402"))
    )
    (comp (ref "R67")
      (value "10k, 0402")
      (footprint "R0402")
      (description "RES SMD 10K OHM 1% 1/16W 0402")
      (fields
        (field (name "MANUFACTURER") "Vishay Dale")
        (field (name "MANUFACTURER PART NUMBER") "CRCW040210K0FKTD")
      )
      (libsource (lib "Miscellaneous Devices") (part "R-Generic-0402"))
    )
    (comp (ref "R68")
      (value "10k, 0402")
      (footprint "R0402")
      (description "RES SMD 10K OHM 1% 1/16W 0402")
      (fields
        (field (name "MANUFACTURER") "Vishay Dale")
        (field (name "MANUFACTURER PART NUMBER") "CRCW040210K0FKTD")
      )
      (libsource (lib "Miscellaneous Devices") (part "R-Generic-0402"))
    )
    (comp (ref "R69")
      (value "330k, 0603")
      (footprint "R0603")
      (description "RES SMD 330K OHM 5% 1/10W 0603")
      (fields
        (field (name "MANUFACTURER") "Yageo")
        (field (name "MANUFACTURER PART NUMBER") "RC0603JR-07330KL")
      )
      (libsource (lib "*") (part "R-Generic-0603"))
    )
    (comp (ref "R70")
      (value "330k, 0603")
      (footprint "R0603")
      (description "RES SMD 330K OHM 5% 1/10W 0603")
      (fields
        (field (name "MANUFACTURER") "Yageo")
        (field (name "MANUFACTURER PART NUMBER") "RC0603JR-07330KL")
      )
      (libsource (lib "*") (part "R-Generic-0603"))
    )
    (comp (ref "R71")
      (value "1k, 0402")
      (footprint "R0402")
      (description "RES SMD 1K OHM 5% 1/16W 0402")
      (fields
        (field (name "MANUFACTURER") "Yageo")
        (field (name "MANUFACTURER PART NUMBER") "RC0402JR-071KL")
      )
      (libsource (lib "*") (part "R-Generic-0402"))
    )
  )
  (nets
    (net (code "1") (name "B0") (class "Default")
      (node (ref "C43") (pin "2") (pinfunction "2_2") (pintype "passive"))
      (node (ref "C45") (pin "2") (pinfunction "2_2") (pintype "passive"))
      (node (ref "Q12") (pin "S") (pinfunction "SOURCE_S") (pintype "passive"))
      (node (ref "R69") (pin "2") (pinfunction "2_2") (pintype "passive"))
      (node (ref "R71") (pin "1") (pinfunction "1_1") (pintype "passive"))
    )
    (net (code "2") (name "B1") (class "Default")
      (node (ref "C37") (pin "2") (pinfunction "2_2") (pintype "passive"))
      (node (ref "C39") (pin "2") (pinfunction "2_2") (pintype "passive"))
      (node (ref "C43") (pin "1") (pinfunction "1_1") (pintype "passive"))
      (node (ref "D13") (pin "A") (pinfunction "ANODE_A") (pintype "passive"))
      (node (ref "Q9") (pin "S") (pinfunction "SOURCE_S") (pintype "passive"))
      (node (ref "R58") (pin "2") (pinfunction "2_2") (pintype "passive"))
      (node (ref "R61") (pin "2") (pinfunction "2_2") (pintype "passive"))
      (node (ref "R64") (pin "1") (pinfunction "1_1") (pintype "passive"))
    )
    (net (code "3") (name "B2") (class "Default")
      (node (ref "C28") (pin "2") (pinfunction "2_2") (pintype "passive"))
      (node (ref "C30") (pin "2") (pinfunction "2_2") (pintype "passive"))
      (node (ref "C37") (pin "1") (pinfunction "1_1") (pintype "passive"))
      (node (ref "D10") (pin "A") (pinfunction "ANODE_A") (pintype "passive"))
      (node (ref "Q6") (pin "S") (pinfunction "SOURCE_S") (pintype "passive"))
      (node (ref "R43") (pin "2") (pinfunction "2_2") (pintype "passive"))
      (node (ref "R46") (pin "2") (pinfunction "2_2") (pintype "passive"))
      (node (ref "R50") (pin "1") (pinfunction "1_1") (pintype "passive"))
    )
    (net (code "4") (name "B3") (class "Default")
      (node (ref "C20") (pin "2") (pinfunction "2_2") (pintype "passive"))
      (node (ref "C21") (pin "2") (pinfunction "2_2") (pintype "passive"))
      (node (ref "C28") (pin "1") (pinfunction "1_1") (pintype "passive"))
      (node (ref "D7") (pin "A") (pinfunction "ANODE_A") (pintype "passive"))
      (node (ref "Q4") (pin "S") (pinfunction "SOURCE_S") (pintype "passive"))
      (node (ref "R29") (pin "2") (pinfunction "2_2") (pintype "passive"))
      (node (ref "R31") (pin "2") (pinfunction "2_2") (pintype "passive"))
      (node (ref "R34") (pin "1") (pinfunction "1_1") (pintype "passive"))
    )
    (net (code "5") (name "B4") (class "Default")
      (node (ref "C15") (pin "2") (pinfunction "2_2") (pintype "passive"))
      (node (ref "C16") (pin "2") (pinfunction "2_2") (pintype "passive"))
      (node (ref "C20") (pin "1") (pinfunction "1_1") (pintype "passive"))
      (node (ref "D5") (pin "A") (pinfunction "ANODE_A") (pintype "passive"))
      (node (ref "Q3") (pin "S") (pinfunction "SOURCE_S") (pintype "passive"))
      (node (ref "R19") (pin "2") (pinfunction "2_2") (pintype "passive"))
      (node (ref "R22") (pin "2") (pinfunction "2_2") (pintype "passive"))
      (node (ref "R25") (pin "1") (pinfunction "1_1") (pintype "passive"))
    )
    (net (code "6") (name "B5") (class "Default")
      (node (ref "C15") (pin "1") (pinfunction "1_1") (pintype "passive"))
      (node (ref "C44") (pin "2") (pinfunction "2_2") (pintype "passive"))
      (node (ref "C46") (pin "2") (pinfunction "2_2") (pintype "passive"))
      (node (ref "D3") (pin "A") (pinfunction "ANODE_A") (pintype "passive"))
      (node (ref "Q13") (pin "S") (pinfunction "SOURCE_S") (pintype "passive"))
      (node (ref "R13") (pin "2") (pinfunction "2_2") (pintype "passive"))
      (node (ref "R16") (pin "1") (pinfunction "1_1") (pintype "passive"))
      (node (ref "R70") (pin "2") (pinfunction "2_2") (pintype "passive"))
    )
    (net (code "7") (name "B6") (class "Default")
      (node (ref "C38") (pin "2") (pinfunction "2_2") (pintype "passive"))
      (node (ref "C40") (pin "2") (pinfunction "2_2") (pintype "passive"))
      (node (ref "C44") (pin "1") (pinfunction "1_1") (pintype "passive"))
      (node (ref "D14") (pin "A") (pinfunction "ANODE_A") (pintype "passive"))
      (node (ref "Q10") (pin "S") (pinfunction "SOURCE_S") (pintype "passive"))
      (node (ref "R59") (pin "2") (pinfunction "2_2") (pintype "passive"))
      (node (ref "R62") (pin "2") (pinfunction "2_2") (pintype "passive"))
      (node (ref "R66") (pin "1") (pinfunction "1_1") (pintype "passive"))
    )
    (net (code "8") (name "B7") (class "Default")
      (node (ref "C29") (pin "2") (pinfunction "2_2") (pintype "passive"))
      (node (ref "C31") (pin "2") (pinfunction "2_2") (pintype "passive"))
      (node (ref "C38") (pin "1") (pinfunction "1_1") (pintype "passive"))
      (node (ref "D11") (pin "A") (pinfunction "ANODE_A") (pintype "passive"))
      (node (ref "Q7") (pin "S") (pinfunction "SOURCE_S") (pintype "passive"))
      (node (ref "R44") (pin "2") (pinfunction "2_2") (pintype "passive"))
      (node (ref "R47") (pin "2") (pinfunction "2_2") (pintype "passive"))
      (node (ref "R52") (pin "1") (pinfunction "1_1") (pintype "passive"))
    )
    (net (code "9") (name "B8") (class "Default")
      (node (ref "C19") (pin "2") (pinfunction "2_2") (pintype "passive"))
      (node (ref "C22") (pin "2") (pinfunction "2_2") (pintype "passive"))
      (node (ref "C29") (pin "1") (pinfunction "1_1") (pintype "passive"))
      (node (ref "D8") (pin "A") (pinfunction "ANODE_A") (pintype "passive"))
      (node (ref "Q5") (pin "S") (pinfunction "SOURCE_S") (pintype "passive"))
      (node (ref "R30") (pin "2") (pinfunction "2_2") (pintype "passive"))
      (node (ref "R32") (pin "2") (pinfunction "2_2") (pintype "passive"))
      (node (ref "R36") (pin "1") (pinfunction "1_1") (pintype "passive"))
    )
    (net (code "10") (name "B9") (class "Default")
      (node (ref "C13") (pin "2") (pinfunction "2_2") (pintype "passive"))
      (node (ref "C19") (pin "1") (pinfunction "1_1") (pintype "passive"))
      (node (ref "D4") (pin "C") (pinfunction "CATHODE_C") (pintype "passive"))
      (node (ref "D6") (pin "A") (pinfunction "ANODE_A") (pintype "passive"))
      (node (ref "R20") (pin "1") (pinfunction "1_1") (pintype "passive"))
      (node (ref "R21") (pin "1") (pinfunction "1_1") (pintype "passive"))
      (node (ref "R23") (pin "2") (pinfunction "2_2") (pintype "passive"))
    )
    (net (code "11") (name "B10") (class "Default")
      (node (ref "C12") (pin "1") (pinfunction "1_1") (pintype "passive"))
      (node (ref "C13") (pin "1") (pinfunction "1_1") (pintype "passive"))
      (node (ref "C36") (pin "2") (pinfunction "2_2") (pintype "passive"))
      (node (ref "D12") (pin "C") (pinfunction "CATHODE_C") (pintype "passive"))
      (node (ref "Q2") (pin "S") (pinfunction "S_S") (pintype "passive"))
      (node (ref "R11") (pin "1") (pinfunction "1_1") (pintype "passive"))
      (node (ref "R12") (pin "1") (pinfunction "1_1") (pintype "passive"))
      (node (ref "R60") (pin "1") (pinfunction "1_1") (pintype "passive"))
    )
    (net (code "12") (name "B11") (class "Default")
      (node (ref "C27") (pin "2") (pinfunction "2_2") (pintype "passive"))
      (node (ref "C33") (pin "1") (pinfunction "1_1") (pintype "passive"))
      (node (ref "C36") (pin "1") (pinfunction "1_1") (pintype "passive"))
      (node (ref "D9") (pin "C") (pinfunction "CATHODE_C") (pintype "passive"))
      (node (ref "Q11") (pin "S") (pinfunction "S_S") (pintype "passive"))
      (node (ref "R45") (pin "1") (pinfunction "1_1") (pintype "passive"))
      (node (ref "R48") (pin "1") (pinfunction "1_1") (pintype "passive"))
      (node (ref "R53") (pin "1") (pinfunction "1_1") (pintype "passive"))
    )
    (net (code "13") (name "B12") (class "Default")
      (node (ref "C26") (pin "1") (pinfunction "1_1") (pintype "passive"))
      (node (ref "C27") (pin "1") (pinfunction "1_1") (pintype "passive"))
      (node (ref "Q8") (pin "S") (pinfunction "S_S") (pintype "passive"))
      (node (ref "R37") (pin "1") (pinfunction "1_1") (pintype "passive"))
      (node (ref "R38") (pin "1") (pinfunction "1_1") (pintype "passive"))
    )
    (net (code "14") (name "CB1") (class "Default")
      (node (ref "R67") (pin "2") (pinfunction "2_2") (pintype "passive"))
    )
    (net (code "15") (name "CB2") (class "Default")
      (node (ref "R55") (pin "2") (pinfunction "2_2") (pintype "passive"))
    )
    (net (code "16") (name "CB3") (class "Default")
      (node (ref "R40") (pin "2") (pinfunction "2_2") (pintype "passive"))
    )
    (net (code "17") (name "CB4") (class "Default")
      (node (ref "R27") (pin "2") (pinfunction "2_2") (pintype "passive"))
    )
    (net (code "18") (name "CB5") (class "Default")
      (node (ref "R18") (pin "2") (pinfunction "2_2") (pintype "passive"))
    )
    (net (code "19") (name "CB6") (class "Default")
      (node (ref "R68") (pin "2") (pinfunction "2_2") (pintype "passive"))
    )
    (net (code "20") (name "CB7") (class "Default")
      (node (ref "R56") (pin "2") (pinfunction "2_2") (pintype "passive"))
    )
    (net (code "21") (name "CB8") (class "Default")
      (node (ref "R41") (pin "2") (pinfunction "2_2") (pintype "passive"))
    )
    (net (code "22") (name "CB9") (class "Default")
      (node (ref "R28") (pin "2") (pinfunction "2_2") (pintype "passive"))
    )
    (net (code "23") (name "CB10") (class "Default")
      (node (ref "R14") (pin "2") (pinfunction "2_2") (pintype "passive"))
    )
    (net (code "24") (name "CB11") (class "Default")
      (node (ref "R54") (pin "2") (pinfunction "2_2") (pintype "passive"))
    )
    (net (code "25") (name "CB12") (class "Default")
      (node (ref "R39") (pin "2") (pinfunction "2_2") (pintype "passive"))
    )
    (net (code "26") (name "GND") (class "Default")
      (node (ref "C11") (pin "2") (pinfunction "2_2") (pintype "passive"))
      (node (ref "C14") (pin "2") (pinfunction "2_2") (pintype "passive"))
      (node (ref "C17") (pin "2") (pinfunction "2_2") (pintype "passive"))
      (node (ref "C18") (pin "2") (pinfunction "2_2") (pintype "passive"))
      (node (ref "C23") (pin "2") (pinfunction "2_2") (pintype "passive"))
      (node (ref "C24") (pin "2") (pinfunction "2_2") (pintype "passive"))
      (node (ref "C25") (pin "2") (pinfunction "2_2") (pintype "passive"))
      (node (ref "C32") (pin "2") (pinfunction "2_2") (pintype "passive"))
      (node (ref "C34") (pin "2") (pinfunction "2_2") (pintype "passive"))
      (node (ref "C35") (pin "2") (pinfunction "2_2") (pintype "passive"))
      (node (ref "C41") (pin "2") (pinfunction "2_2") (pintype "passive"))
      (node (ref "C42") (pin "2") (pinfunction "2_2") (pintype "passive"))
      (node (ref "C47") (pin "2") (pinfunction "2_2") (pintype "passive"))
    )
    (net (code "27") (name "Net-(C12-Pad2)") (class "Default")
      (node (ref "C12") (pin "2") (pinfunction "2_2") (pintype "passive"))
      (node (ref "Q2") (pin "G") (pinfunction "G_G") (pintype "passive"))
      (node (ref "R12") (pin "2") (pinfunction "2_2") (pintype "passive"))
      (node (ref "R14") (pin "1") (pinfunction "1_1") (pintype "passive"))
    )
    (net (code "28") (name "Net-(C26-Pad2)") (class "Default")
      (node (ref "C26") (pin "2") (pinfunction "2_2") (pintype "passive"))
      (node (ref "Q8") (pin "G") (pinfunction "G_G") (pintype "passive"))
      (node (ref "R38") (pin "2") (pinfunction "2_2") (pintype "passive"))
      (node (ref "R39") (pin "1") (pinfunction "1_1") (pintype "passive"))
    )
    (net (code "29") (name "Net-(C33-Pad2)") (class "Default")
      (node (ref "C33") (pin "2") (pinfunction "2_2") (pintype "passive"))
      (node (ref "Q11") (pin "G") (pinfunction "G_G") (pintype "passive"))
      (node (ref "R53") (pin "2") (pinfunction "2_2") (pintype "passive"))
      (node (ref "R54") (pin "1") (pinfunction "1_1") (pintype "passive"))
    )
    (net (code "30") (name "Net-(D3-CATHODE)") (class "Default")
      (node (ref "D3") (pin "C") (pinfunction "CATHODE_C") (pintype "passive"))
      (node (ref "R15") (pin "1") (pinfunction "1_1") (pintype "passive"))
    )
    (net (code "31") (name "Net-(D4-ANODE)") (class "Default")
      (node (ref "D4") (pin "A") (pinfunction "ANODE_A") (pintype "passive"))
      (node (ref "R17") (pin "1") (pinfunction "1_1") (pintype "passive"))
    )
    (net (code "32") (name "Net-(D5-CATHODE)") (class "Default")
      (node (ref "D5") (pin "C") (pinfunction "CATHODE_C") (pintype "passive"))
      (node (ref "R24") (pin "1") (pinfunction "1_1") (pintype "passive"))
    )
    (net (code "33") (name "Net-(D6-CATHODE)") (class "Default")
      (node (ref "D6") (pin "C") (pinfunction "CATHODE_C") (pintype "passive"))
      (node (ref "R26") (pin "1") (pinfunction "1_1") (pintype "passive"))
    )
    (net (code "34") (name "Net-(D7-CATHODE)") (class "Default")
      (node (ref "D7") (pin "C") (pinfunction "CATHODE_C") (pintype "passive"))
      (node (ref "R33") (pin "1") (pinfunction "1_1") (pintype "passive"))
    )
    (net (code "35") (name "Net-(D8-CATHODE)") (class "Default")
      (node (ref "D8") (pin "C") (pinfunction "CATHODE_C") (pintype "passive"))
      (node (ref "R35") (pin "1") (pinfunction "1_1") (pintype "passive"))
    )
    (net (code "36") (name "Net-(D9-ANODE)") (class "Default")
      (node (ref "D9") (pin "A") (pinfunction "ANODE_A") (pintype "passive"))
      (node (ref "R42") (pin "1") (pinfunction "1_1") (pintype "passive"))
    )
    (net (code "37") (name "Net-(D10-CATHODE)") (class "Default")
      (node (ref "D10") (pin "C") (pinfunction "CATHODE_C") (pintype "passive"))
      (node (ref "R49") (pin "1") (pinfunction "1_1") (pintype "passive"))
    )
    (net (code "38") (name "Net-(D11-CATHODE)") (class "Default")
      (node (ref "D11") (pin "C") (pinfunction "CATHODE_C") (pintype "passive"))
      (node (ref "R51") (pin "1") (pinfunction "1_1") (pintype "passive"))
    )
    (net (code "39") (name "Net-(D12-ANODE)") (class "Default")
      (node (ref "D12") (pin "A") (pinfunction "ANODE_A") (pintype "passive"))
      (node (ref "R57") (pin "1") (pinfunction "1_1") (pintype "passive"))
    )
    (net (code "40") (name "Net-(D13-CATHODE)") (class "Default")
      (node (ref "D13") (pin "C") (pinfunction "CATHODE_C") (pintype "passive"))
      (node (ref "R63") (pin "1") (pinfunction "1_1") (pintype "passive"))
    )
    (net (code "41") (name "Net-(D14-CATHODE)") (class "Default")
      (node (ref "D14") (pin "C") (pinfunction "CATHODE_C") (pintype "passive"))
      (node (ref "R65") (pin "1") (pinfunction "1_1") (pintype "passive"))
    )
    (net (code "42") (name "Net-(Q2-PadD)") (class "Default")
      (node (ref "Q2") (pin "D") (pinfunction "D_D") (pintype "passive"))
      (node (ref "R17") (pin "2") (pinfunction "2_2") (pintype "passive"))
      (node (ref "R20") (pin "2") (pinfunction "2_2") (pintype "passive"))
    )
    (net (code "43") (name "Net-(Q3-DRAIN)") (class "Default")
      (node (ref "Q3") (pin "D") (pinfunction "DRAIN_D") (pintype "passive"))
      (node (ref "R13") (pin "1") (pinfunction "1_1") (pintype "passive"))
      (node (ref "R15") (pin "2") (pinfunction "2_2") (pintype "passive"))
    )
    (net (code "44") (name "Net-(Q3-GATE)") (class "Default")
      (node (ref "C16") (pin "1") (pinfunction "1_1") (pintype "passive"))
      (node (ref "Q3") (pin "G") (pinfunction "GATE_G") (pintype "passive"))
      (node (ref "R18") (pin "1") (pinfunction "1_1") (pintype "passive"))
      (node (ref "R19") (pin "1") (pinfunction "1_1") (pintype "passive"))
    )
    (net (code "45") (name "Net-(Q4-DRAIN)") (class "Default")
      (node (ref "Q4") (pin "D") (pinfunction "DRAIN_D") (pintype "passive"))
      (node (ref "R22") (pin "1") (pinfunction "1_1") (pintype "passive"))
      (node (ref "R24") (pin "2") (pinfunction "2_2") (pintype "passive"))
    )
    (net (code "46") (name "Net-(Q4-GATE)") (class "Default")
      (node (ref "C21") (pin "1") (pinfunction "1_1") (pintype "passive"))
      (node (ref "Q4") (pin "G") (pinfunction "GATE_G") (pintype "passive"))
      (node (ref "R27") (pin "1") (pinfunction "1_1") (pintype "passive"))
      (node (ref "R29") (pin "1") (pinfunction "1_1") (pintype "passive"))
    )
    (net (code "47") (name "Net-(Q5-DRAIN)") (class "Default")
      (node (ref "Q5") (pin "D") (pinfunction "DRAIN_D") (pintype "passive"))
      (node (ref "R23") (pin "1") (pinfunction "1_1") (pintype "passive"))
      (node (ref "R26") (pin "2") (pinfunction "2_2") (pintype "passive"))
    )
    (net (code "48") (name "Net-(Q5-GATE)") (class "Default")
      (node (ref "C22") (pin "1") (pinfunction "1_1") (pintype "passive"))
      (node (ref "Q5") (pin "G") (pinfunction "GATE_G") (pintype "passive"))
      (node (ref "R28") (pin "1") (pinfunction "1_1") (pintype "passive"))
      (node (ref "R30") (pin "1") (pinfunction "1_1") (pintype "passive"))
    )
    (net (code "49") (name "Net-(Q6-DRAIN)") (class "Default")
      (node (ref "Q6") (pin "D") (pinfunction "DRAIN_D") (pintype "passive"))
      (node (ref "R31") (pin "1") (pinfunction "1_1") (pintype "passive"))
      (node (ref "R33") (pin "2") (pinfunction "2_2") (pintype "passive"))
    )
    (net (code "50") (name "Net-(Q6-GATE)") (class "Default")
      (node (ref "C30") (pin "1") (pinfunction "1_1") (pintype "passive"))
      (node (ref "Q6") (pin "G") (pinfunction "GATE_G") (pintype "passive"))
      (node (ref "R40") (pin "1") (pinfunction "1_1") (pintype "passive"))
      (node (ref "R43") (pin "1") (pinfunction "1_1") (pintype "passive"))
    )
    (net (code "51") (name "Net-(Q7-DRAIN)") (class "Default")
      (node (ref "Q7") (pin "D") (pinfunction "DRAIN_D") (pintype "passive"))
      (node (ref "R32") (pin "1") (pinfunction "1_1") (pintype "passive"))
      (node (ref "R35") (pin "2") (pinfunction "2_2") (pintype "passive"))
    )
    (net (code "52") (name "Net-(Q7-GATE)") (class "Default")
      (node (ref "C31") (pin "1") (pinfunction "1_1") (pintype "passive"))
      (node (ref "Q7") (pin "G") (pinfunction "GATE_G") (pintype "passive"))
      (node (ref "R41") (pin "1") (pinfunction "1_1") (pintype "passive"))
      (node (ref "R44") (pin "1") (pinfunction "1_1") (pintype "passive"))
    )
    (net (code "53") (name "Net-(Q8-PadD)") (class "Default")
      (node (ref "Q8") (pin "D") (pinfunction "D_D") (pintype "passive"))
      (node (ref "R42") (pin "2") (pinfunction "2_2") (pintype "passive"))
      (node (ref "R45") (pin "2") (pinfunction "2_2") (pintype "passive"))
    )
    (net (code "54") (name "Net-(Q9-DRAIN)") (class "Default")
      (node (ref "Q9") (pin "D") (pinfunction "DRAIN_D") (pintype "passive"))
      (node (ref "R46") (pin "1") (pinfunction "1_1") (pintype "passive"))
      (node (ref "R49") (pin "2") (pinfunction "2_2") (pintype "passive"))
    )
    (net (code "55") (name "Net-(Q9-GATE)") (class "Default")
      (node (ref "C39") (pin "1") (pinfunction "1_1") (pintype "passive"))
      (node (ref "Q9") (pin "G") (pinfunction "GATE_G") (pintype "passive"))
      (node (ref "R55") (pin "1") (pinfunction "1_1") (pintype "passive"))
      (node (ref "R58") (pin "1") (pinfunction "1_1") (pintype "passive"))
    )
    (net (code "56") (name "Net-(Q10-DRAIN)") (class "Default")
      (node (ref "Q10") (pin "D") (pinfunction "DRAIN_D") (pintype "passive"))
      (node (ref "R47") (pin "1") (pinfunction "1_1") (pintype "passive"))
      (node (ref "R51") (pin "2") (pinfunction "2_2") (pintype "passive"))
    )
    (net (code "57") (name "Net-(Q10-GATE)") (class "Default")
      (node (ref "C40") (pin "1") (pinfunction "1_1") (pintype "passive"))
      (node (ref "Q10") (pin "G") (pinfunction "GATE_G") (pintype "passive"))
      (node (ref "R56") (pin "1") (pinfunction "1_1") (pintype "passive"))
      (node (ref "R59") (pin "1") (pinfunction "1_1") (pintype "passive"))
    )
    (net (code "58") (name "Net-(Q11-PadD)") (class "Default")
      (node (ref "Q11") (pin "D") (pinfunction "D_D") (pintype "passive"))
      (node (ref "R57") (pin "2") (pinfunction "2_2") (pintype "passive"))
      (node (ref "R60") (pin "2") (pinfunction "2_2") (pintype "passive"))
    )
    (net (code "59") (name "Net-(Q12-DRAIN)") (class "Default")
      (node (ref "Q12") (pin "D") (pinfunction "DRAIN_D") (pintype "passive"))
      (node (ref "R61") (pin "1") (pinfunction "1_1") (pintype "passive"))
      (node (ref "R63") (pin "2") (pinfunction "2_2") (pintype "passive"))
    )
    (net (code "60") (name "Net-(Q12-GATE)") (class "Default")
      (node (ref "C45") (pin "1") (pinfunction "1_1") (pintype "passive"))
      (node (ref "Q12") (pin "G") (pinfunction "GATE_G") (pintype "passive"))
      (node (ref "R67") (pin "1") (pinfunction "1_1") (pintype "passive"))
      (node (ref "R69") (pin "1") (pinfunction "1_1") (pintype "passive"))
    )
    (net (code "61") (name "Net-(Q13-DRAIN)") (class "Default")
      (node (ref "Q13") (pin "D") (pinfunction "DRAIN_D") (pintype "passive"))
      (node (ref "R62") (pin "1") (pinfunction "1_1") (pintype "passive"))
      (node (ref "R65") (pin "2") (pinfunction "2_2") (pintype "passive"))
    )
    (net (code "62") (name "Net-(Q13-GATE)") (class "Default")
      (node (ref "C46") (pin "1") (pinfunction "1_1") (pintype "passive"))
      (node (ref "Q13") (pin "G") (pinfunction "GATE_G") (pintype "passive"))
      (node (ref "R68") (pin "1") (pinfunction "1_1") (pintype "passive"))
      (node (ref "R70") (pin "1") (pinfunction "1_1") (pintype "passive"))
    )
    (net (code "63") (name "VC0") (class "Default")
      (node (ref "C47") (pin "1") (pinfunction "1_1") (pintype "passive"))
      (node (ref "R71") (pin "2") (pinfunction "2_2") (pintype "passive"))
    )
    (net (code "64") (name "VC1") (class "Default")
      (node (ref "C41") (pin "1") (pinfunction "1_1") (pintype "passive"))
      (node (ref "R64") (pin "2") (pinfunction "2_2") (pintype "passive"))
    )
    (net (code "65") (name "VC2") (class "Default")
      (node (ref "C34") (pin "1") (pinfunction "1_1") (pintype "passive"))
      (node (ref "R50") (pin "2") (pinfunction "2_2") (pintype "passive"))
    )
    (net (code "66") (name "VC3") (class "Default")
      (node (ref "C24") (pin "1") (pinfunction "1_1") (pintype "passive"))
      (node (ref "R34") (pin "2") (pinfunction "2_2") (pintype "passive"))
    )
    (net (code "67") (name "VC4") (class "Default")
      (node (ref "C18") (pin "1") (pinfunction "1_1") (pintype "passive"))
      (node (ref "R25") (pin "2") (pinfunction "2_2") (pintype "passive"))
    )
    (net (code "68") (name "VC5") (class "Default")
      (node (ref "C14") (pin "1") (pinfunction "1_1") (pintype "passive"))
      (node (ref "R16") (pin "2") (pinfunction "2_2") (pintype "passive"))
    )
    (net (code "69") (name "VC6") (class "Default")
      (node (ref "C42") (pin "1") (pinfunction "1_1") (pintype "passive"))
      (node (ref "R66") (pin "2") (pinfunction "2_2") (pintype "passive"))
    )
    (net (code "70") (name "VC7") (class "Default")
      (node (ref "C35") (pin "1") (pinfunction "1_1") (pintype "passive"))
      (node (ref "R52") (pin "2") (pinfunction "2_2") (pintype "passive"))
    )
    (net (code "71") (name "VC8") (class "Default")
      (node (ref "C25") (pin "1") (pinfunction "1_1") (pintype "passive"))
      (node (ref "R36") (pin "2") (pinfunction "2_2") (pintype "passive"))
    )
    (net (code "72") (name "VC9") (class "Default")
      (node (ref "C17") (pin "1") (pinfunction "1_1") (pintype "passive"))
      (node (ref "R21") (pin "2") (pinfunction "2_2") (pintype "passive"))
    )
    (net (code "73") (name "VC10") (class "Default")
      (node (ref "C11") (pin "1") (pinfunction "1_1") (pintype "passive"))
      (node (ref "R11") (pin "2") (pinfunction "2_2") (pintype "passive"))
    )
    (net (code "74") (name "VC11") (class "Default")
      (node (ref "C32") (pin "1") (pinfunction "1_1") (pintype "passive"))
      (node (ref "R48") (pin "2") (pinfunction "2_2") (pintype "passive"))
    )
    (net (code "75") (name "VC12") (class "Default")
      (node (ref "C23") (pin "1") (pinfunction "1_1") (pintype "passive"))
      (node (ref "R37") (pin "2") (pinfunction "2_2") (pintype "passive"))
    )
  )
)
